# Sensors_aux.net
KiCad netlist of a schematic drawn in Altium Designer
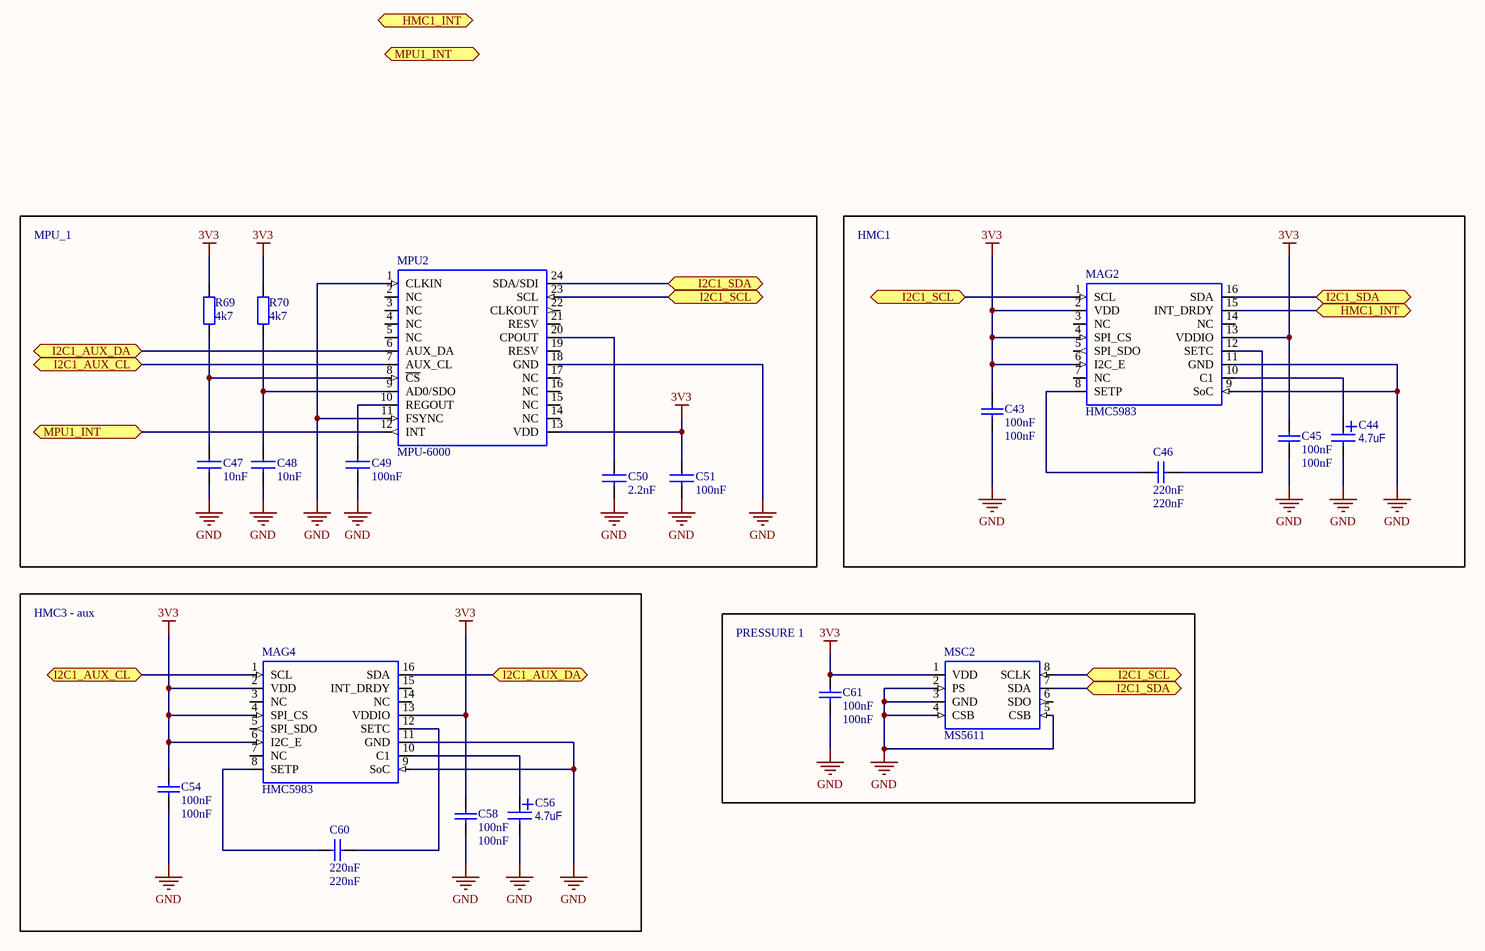
[diagram p0: Sensors_aux.SchDoc]

(export (version "E")
  (design (tool "Eeschema 10.0.6"))
  (components
    (comp (ref "C43")
      (value "100nF")
      (footprint "080503")
      (description "CAP CER 0.1UF 25V 10% X7R 0805")
      (fields (field (name "ALTIUM_VALUE") "100nF"))
      (libsource (lib "Miscellaneous Devices") (part "Cap"))
    )
    (comp (ref "C44")
      (value "4.7uF")
      (footprint "120605")
      (description "CAP TANT 4.7uF 10V 10% 1206")
      (libsource (lib "EISI") (part "CAPA_T"))
    )
    (comp (ref "C45")
      (value "100nF")
      (footprint "080503")
      (description "CAP CER 0.1UF 25V 10% X7R 0805")
      (fields (field (name "ALTIUM_VALUE") "100nF"))
      (libsource (lib "Miscellaneous Devices") (part "Cap"))
    )
    (comp (ref "C46")
      (value "220nF")
      (footprint "080503")
      (description "CAP CER 0.22uF 50V X7R 10% 0805")
      (fields (field (name "ALTIUM_VALUE") "220nF"))
      (libsource (lib "Miscellaneous Devices") (part "Cap"))
    )
    (comp (ref "C47")
      (value "10nF")
      (footprint "080503")
      (description "CAP CER 10nF 50V 10% X7R 0805")
      (libsource (lib "EISI") (part "CAPA"))
    )
    (comp (ref "C48")
      (value "10nF")
      (footprint "080503")
      (description "CAP CER 10nF 50V 10% X7R 0805")
      (libsource (lib "EISI") (part "CAPA"))
    )
    (comp (ref "C49")
      (value "100nF")
      (footprint "080503")
      (description "CAP CER 0.1UF 25V 10% X7R 0805")
      (libsource (lib "EISI") (part "CAPA"))
    )
    (comp (ref "C50")
      (value "2.2nF")
      (footprint "080503")
      (description "CAP CER 2.2nF 50V")
      (libsource (lib "EISI") (part "CAPA"))
    )
    (comp (ref "C51")
      (value "100nF")
      (footprint "080503")
      (description "CAP CER 0.1UF 25V 10% X7R 0805")
      (libsource (lib "EISI") (part "CAPA"))
    )
    (comp (ref "C54")
      (value "100nF")
      (footprint "080503")
      (description "CAP CER 0.1UF 25V 10% X7R 0805")
      (fields (field (name "ALTIUM_VALUE") "100nF"))
      (libsource (lib "Miscellaneous Devices") (part "Cap"))
    )
    (comp (ref "C56")
      (value "4.7uF")
      (footprint "120605")
      (description "CAP TANT 4.7uF 10V 10% 1206")
      (libsource (lib "EISI") (part "CAPA_T"))
    )
    (comp (ref "C58")
      (value "100nF")
      (footprint "080503")
      (description "CAP CER 0.1UF 25V 10% X7R 0805")
      (fields (field (name "ALTIUM_VALUE") "100nF"))
      (libsource (lib "Miscellaneous Devices") (part "Cap"))
    )
    (comp (ref "C60")
      (value "220nF")
      (footprint "080503")
      (description "CAP CER 0.22uF 50V X7R 10% 0805")
      (fields (field (name "ALTIUM_VALUE") "220nF"))
      (libsource (lib "Miscellaneous Devices") (part "Cap"))
    )
    (comp (ref "C61")
      (value "100nF")
      (footprint "080503")
      (description "CAP CER 0.1UF 25V 10% X7R 0805")
      (fields (field (name "ALTIUM_VALUE") "100nF"))
      (libsource (lib "Miscellaneous Devices") (part "Cap"))
    )
    (comp (ref "MAG2")
      (value "HMC5983")
      (footprint "QFN16")
      (description "HMC5983 MAGNETOMETER")
      (libsource (lib "Aeroval") (part "HMC5983"))
    )
    (comp (ref "MAG4")
      (value "HMC5983")
      (footprint "QFN16")
      (description "HMC5983 MAGNETOMETER")
      (libsource (lib "Aeroval") (part "HMC5983"))
    )
    (comp (ref "MPU2")
      (value "MPU-6000")
      (footprint "QFN24")
      (description "MPU-6000 MOTION PROCESSOR")
      (libsource (lib "Aeroval") (part "MPU-6000"))
    )
    (comp (ref "MSC2")
      (value "MS5611")
      (footprint "MS5611")
      (description "MS5611 PRESSURE SENSOR")
      (libsource (lib "Aeroval") (part "MS5611"))
    )
    (comp (ref "R69")
      (value "4k7")
      (footprint "080503")
      (description "RES 4.7K 0805")
      (libsource (lib "EISI") (part "RES"))
    )
    (comp (ref "R70")
      (value "4k7")
      (footprint "080503")
      (description "RES 4.7K 0805")
      (libsource (lib "EISI") (part "RES"))
    )
  )
  (nets
    (net (code "1") (name "/HMC1_INT") (class "Default")
      (node (ref "MAG2") (pin "15") (pinfunction "INT_DRDY_15") (pintype "power_in"))
    )
    (net (code "2") (name "/I2C1_AUX_CL") (class "Default")
      (node (ref "MAG4") (pin "1") (pinfunction "SCL_1") (pintype "input"))
      (node (ref "MPU2") (pin "7") (pinfunction "AUX_CL_7") (pintype "bidirectional"))
    )
    (net (code "3") (name "/I2C1_AUX_DA") (class "Default")
      (node (ref "MAG4") (pin "16") (pinfunction "SDA_16") (pintype "bidirectional"))
      (node (ref "MPU2") (pin "6") (pinfunction "AUX_DA_6") (pintype "bidirectional"))
    )
    (net (code "4") (name "/I2C1_SCL") (class "Default")
      (node (ref "MAG2") (pin "1") (pinfunction "SCL_1") (pintype "input"))
      (node (ref "MPU2") (pin "23") (pinfunction "SCL_23") (pintype "input"))
      (node (ref "MSC2") (pin "8") (pinfunction "SCLK_8") (pintype "input"))
    )
    (net (code "5") (name "/I2C1_SDA") (class "Default")
      (node (ref "MAG2") (pin "16") (pinfunction "SDA_16") (pintype "bidirectional"))
      (node (ref "MPU2") (pin "24") (pinfunction "SDA/SDI_24") (pintype "bidirectional"))
      (node (ref "MSC2") (pin "7") (pinfunction "SDA_7") (pintype "bidirectional"))
    )
    (net (code "6") (name "/MPU1_INT") (class "Default")
      (node (ref "MPU2") (pin "12") (pinfunction "INT_12") (pintype "output"))
    )
    (net (code "7") (name "3V3") (class "Default")
      (node (ref "C43") (pin "1") (pinfunction "1_1") (pintype "passive"))
      (node (ref "C45") (pin "1") (pinfunction "1_1") (pintype "passive"))
      (node (ref "C51") (pin "1") (pinfunction "1_1") (pintype "passive"))
      (node (ref "C54") (pin "1") (pinfunction "1_1") (pintype "passive"))
      (node (ref "C58") (pin "1") (pinfunction "1_1") (pintype "passive"))
      (node (ref "C61") (pin "2") (pinfunction "2_2") (pintype "passive"))
      (node (ref "MAG2") (pin "13") (pinfunction "VDDIO_13") (pintype "power_in"))
      (node (ref "MAG2") (pin "2") (pinfunction "VDD_2") (pintype "power_in"))
      (node (ref "MAG2") (pin "4") (pinfunction "SPI_CS_4") (pintype "input"))
      (node (ref "MAG2") (pin "6") (pinfunction "I2C_E_6") (pintype "input"))
      (node (ref "MAG4") (pin "13") (pinfunction "VDDIO_13") (pintype "power_in"))
      (node (ref "MAG4") (pin "2") (pinfunction "VDD_2") (pintype "power_in"))
      (node (ref "MAG4") (pin "4") (pinfunction "SPI_CS_4") (pintype "input"))
      (node (ref "MAG4") (pin "6") (pinfunction "I2C_E_6") (pintype "input"))
      (node (ref "MPU2") (pin "13") (pinfunction "VDD_13") (pintype "power_in"))
      (node (ref "MSC2") (pin "1") (pinfunction "VDD_1") (pintype "power_in"))
      (node (ref "R69") (pin "2") (pinfunction "2_2") (pintype "passive"))
      (node (ref "R70") (pin "2") (pinfunction "2_2") (pintype "passive"))
    )
    (net (code "8") (name "GND") (class "Default")
      (node (ref "C43") (pin "2") (pinfunction "2_2") (pintype "passive"))
      (node (ref "C44") (pin "2") (pinfunction "2_2") (pintype "passive"))
      (node (ref "C45") (pin "2") (pinfunction "2_2") (pintype "passive"))
      (node (ref "C47") (pin "2") (pinfunction "2_2") (pintype "passive"))
      (node (ref "C48") (pin "2") (pinfunction "2_2") (pintype "passive"))
      (node (ref "C49") (pin "2") (pinfunction "2_2") (pintype "passive"))
      (node (ref "C50") (pin "2") (pinfunction "2_2") (pintype "passive"))
      (node (ref "C51") (pin "2") (pinfunction "2_2") (pintype "passive"))
      (node (ref "C54") (pin "2") (pinfunction "2_2") (pintype "passive"))
      (node (ref "C56") (pin "2") (pinfunction "2_2") (pintype "passive"))
      (node (ref "C58") (pin "2") (pinfunction "2_2") (pintype "passive"))
      (node (ref "C61") (pin "1") (pinfunction "1_1") (pintype "passive"))
      (node (ref "MAG2") (pin "11") (pinfunction "GND_11") (pintype "power_in"))
      (node (ref "MAG2") (pin "9") (pinfunction "SoC_9") (pintype "input"))
      (node (ref "MAG4") (pin "11") (pinfunction "GND_11") (pintype "power_in"))
      (node (ref "MAG4") (pin "9") (pinfunction "SoC_9") (pintype "input"))
      (node (ref "MPU2") (pin "1") (pinfunction "CLKIN_1") (pintype "input"))
      (node (ref "MPU2") (pin "11") (pinfunction "FSYNC_11") (pintype "input"))
      (node (ref "MPU2") (pin "18") (pinfunction "GND_18") (pintype "power_in"))
      (node (ref "MSC2") (pin "2") (pinfunction "PS_2") (pintype "input"))
      (node (ref "MSC2") (pin "3") (pinfunction "GND_3") (pintype "power_in"))
      (node (ref "MSC2") (pin "4") (pinfunction "CSB_4") (pintype "input"))
      (node (ref "MSC2") (pin "5") (pinfunction "CSB_5") (pintype "input"))
    )
    (net (code "9") (name "Net-(MAG2-C1)") (class "Default")
      (node (ref "C44") (pin "1") (pinfunction "1_1") (pintype "passive"))
      (node (ref "MAG2") (pin "10") (pinfunction "C1_10") (pintype "power_in"))
    )
    (net (code "10") (name "Net-(MAG2-SETC)") (class "Default")
      (node (ref "C46") (pin "1") (pinfunction "1_1") (pintype "passive"))
      (node (ref "MAG2") (pin "12") (pinfunction "SETC_12") (pintype "power_in"))
    )
    (net (code "11") (name "Net-(MAG2-SETP)") (class "Default")
      (node (ref "C46") (pin "2") (pinfunction "2_2") (pintype "passive"))
      (node (ref "MAG2") (pin "8") (pinfunction "SETP_8") (pintype "power_in"))
    )
    (net (code "12") (name "Net-(MAG4-C1)") (class "Default")
      (node (ref "C56") (pin "1") (pinfunction "1_1") (pintype "passive"))
      (node (ref "MAG4") (pin "10") (pinfunction "C1_10") (pintype "power_in"))
    )
    (net (code "13") (name "Net-(MAG4-SETC)") (class "Default")
      (node (ref "C60") (pin "1") (pinfunction "1_1") (pintype "passive"))
      (node (ref "MAG4") (pin "12") (pinfunction "SETC_12") (pintype "power_in"))
    )
    (net (code "14") (name "Net-(MAG4-SETP)") (class "Default")
      (node (ref "C60") (pin "2") (pinfunction "2_2") (pintype "passive"))
      (node (ref "MAG4") (pin "8") (pinfunction "SETP_8") (pintype "power_in"))
    )
    (net (code "15") (name "Net-(MPU2-AD0{slash}SDO)") (class "Default")
      (node (ref "C48") (pin "1") (pinfunction "1_1") (pintype "passive"))
      (node (ref "MPU2") (pin "9") (pinfunction "AD0/SDO_9") (pintype "bidirectional"))
      (node (ref "R70") (pin "1") (pinfunction "1_1") (pintype "passive"))
    )
    (net (code "16") (name "Net-(MPU2-CPOUT)") (class "Default")
      (node (ref "C50") (pin "1") (pinfunction "1_1") (pintype "passive"))
      (node (ref "MPU2") (pin "20") (pinfunction "CPOUT_20") (pintype "power_in"))
    )
    (net (code "17") (name "Net-(MPU2-REGOUT)") (class "Default")
      (node (ref "C49") (pin "1") (pinfunction "1_1") (pintype "passive"))
      (node (ref "MPU2") (pin "10") (pinfunction "REGOUT_10") (pintype "power_in"))
    )
    (net (code "18") (name "Net-(MPU2-~{CS})") (class "Default")
      (node (ref "C47") (pin "1") (pinfunction "1_1") (pintype "passive"))
      (node (ref "MPU2") (pin "8") (pinfunction "~{CS}_8") (pintype "input"))
      (node (ref "R69") (pin "1") (pinfunction "1_1") (pintype "passive"))
    )
    (net (code "19") (name "unconnected-(MAG2-NC-Pad3)") (class "Default")
      (node (ref "MAG2") (pin "3") (pinfunction "NC_3") (pintype "power_in"))
    )
    (net (code "20") (name "unconnected-(MAG2-NC-Pad7)") (class "Default")
      (node (ref "MAG2") (pin "7") (pinfunction "NC_7") (pintype "power_in"))
    )
    (net (code "21") (name "unconnected-(MAG2-NC-Pad14)") (class "Default")
      (node (ref "MAG2") (pin "14") (pinfunction "NC_14") (pintype "power_in"))
    )
    (net (code "22") (name "unconnected-(MAG2-SPI_SDO-Pad5)") (class "Default")
      (node (ref "MAG2") (pin "5") (pinfunction "SPI_SDO_5") (pintype "output"))
    )
    (net (code "23") (name "unconnected-(MAG4-INT_DRDY-Pad15)") (class "Default")
      (node (ref "MAG4") (pin "15") (pinfunction "INT_DRDY_15") (pintype "power_in"))
    )
    (net (code "24") (name "unconnected-(MAG4-NC-Pad3)") (class "Default")
      (node (ref "MAG4") (pin "3") (pinfunction "NC_3") (pintype "power_in"))
    )
    (net (code "25") (name "unconnected-(MAG4-NC-Pad7)") (class "Default")
      (node (ref "MAG4") (pin "7") (pinfunction "NC_7") (pintype "power_in"))
    )
    (net (code "26") (name "unconnected-(MAG4-NC-Pad14)") (class "Default")
      (node (ref "MAG4") (pin "14") (pinfunction "NC_14") (pintype "power_in"))
    )
    (net (code "27") (name "unconnected-(MAG4-SPI_SDO-Pad5)") (class "Default")
      (node (ref "MAG4") (pin "5") (pinfunction "SPI_SDO_5") (pintype "output"))
    )
    (net (code "28") (name "unconnected-(MPU2-CLKOUT-Pad22)") (class "Default")
      (node (ref "MPU2") (pin "22") (pinfunction "CLKOUT_22") (pintype "output"))
    )
    (net (code "29") (name "unconnected-(MPU2-NC-Pad2)") (class "Default")
      (node (ref "MPU2") (pin "2") (pinfunction "NC_2") (pintype "power_in"))
    )
    (net (code "30") (name "unconnected-(MPU2-NC-Pad3)") (class "Default")
      (node (ref "MPU2") (pin "3") (pinfunction "NC_3") (pintype "power_in"))
    )
    (net (code "31") (name "unconnected-(MPU2-NC-Pad4)") (class "Default")
      (node (ref "MPU2") (pin "4") (pinfunction "NC_4") (pintype "power_in"))
    )
    (net (code "32") (name "unconnected-(MPU2-NC-Pad5)") (class "Default")
      (node (ref "MPU2") (pin "5") (pinfunction "NC_5") (pintype "power_in"))
    )
    (net (code "33") (name "unconnected-(MPU2-NC-Pad14)") (class "Default")
      (node (ref "MPU2") (pin "14") (pinfunction "NC_14") (pintype "power_in"))
    )
    (net (code "34") (name "unconnected-(MPU2-NC-Pad15)") (class "Default")
      (node (ref "MPU2") (pin "15") (pinfunction "NC_15") (pintype "power_in"))
    )
    (net (code "35") (name "unconnected-(MPU2-NC-Pad16)") (class "Default")
      (node (ref "MPU2") (pin "16") (pinfunction "NC_16") (pintype "power_in"))
    )
    (net (code "36") (name "unconnected-(MPU2-NC-Pad17)") (class "Default")
      (node (ref "MPU2") (pin "17") (pinfunction "NC_17") (pintype "power_in"))
    )
    (net (code "37") (name "unconnected-(MPU2-RESV-Pad19)") (class "Default")
      (node (ref "MPU2") (pin "19") (pinfunction "RESV_19") (pintype "power_in"))
    )
    (net (code "38") (name "unconnected-(MPU2-RESV-Pad21)") (class "Default")
      (node (ref "MPU2") (pin "21") (pinfunction "RESV_21") (pintype "power_in"))
    )
    (net (code "39") (name "unconnected-(MSC2-SDO-Pad6)") (class "Default")
      (node (ref "MSC2") (pin "6") (pinfunction "SDO_6") (pintype "output"))
    )
  )
)
